# Microcontroller.net
KiCad netlist of a schematic drawn in Altium Designer
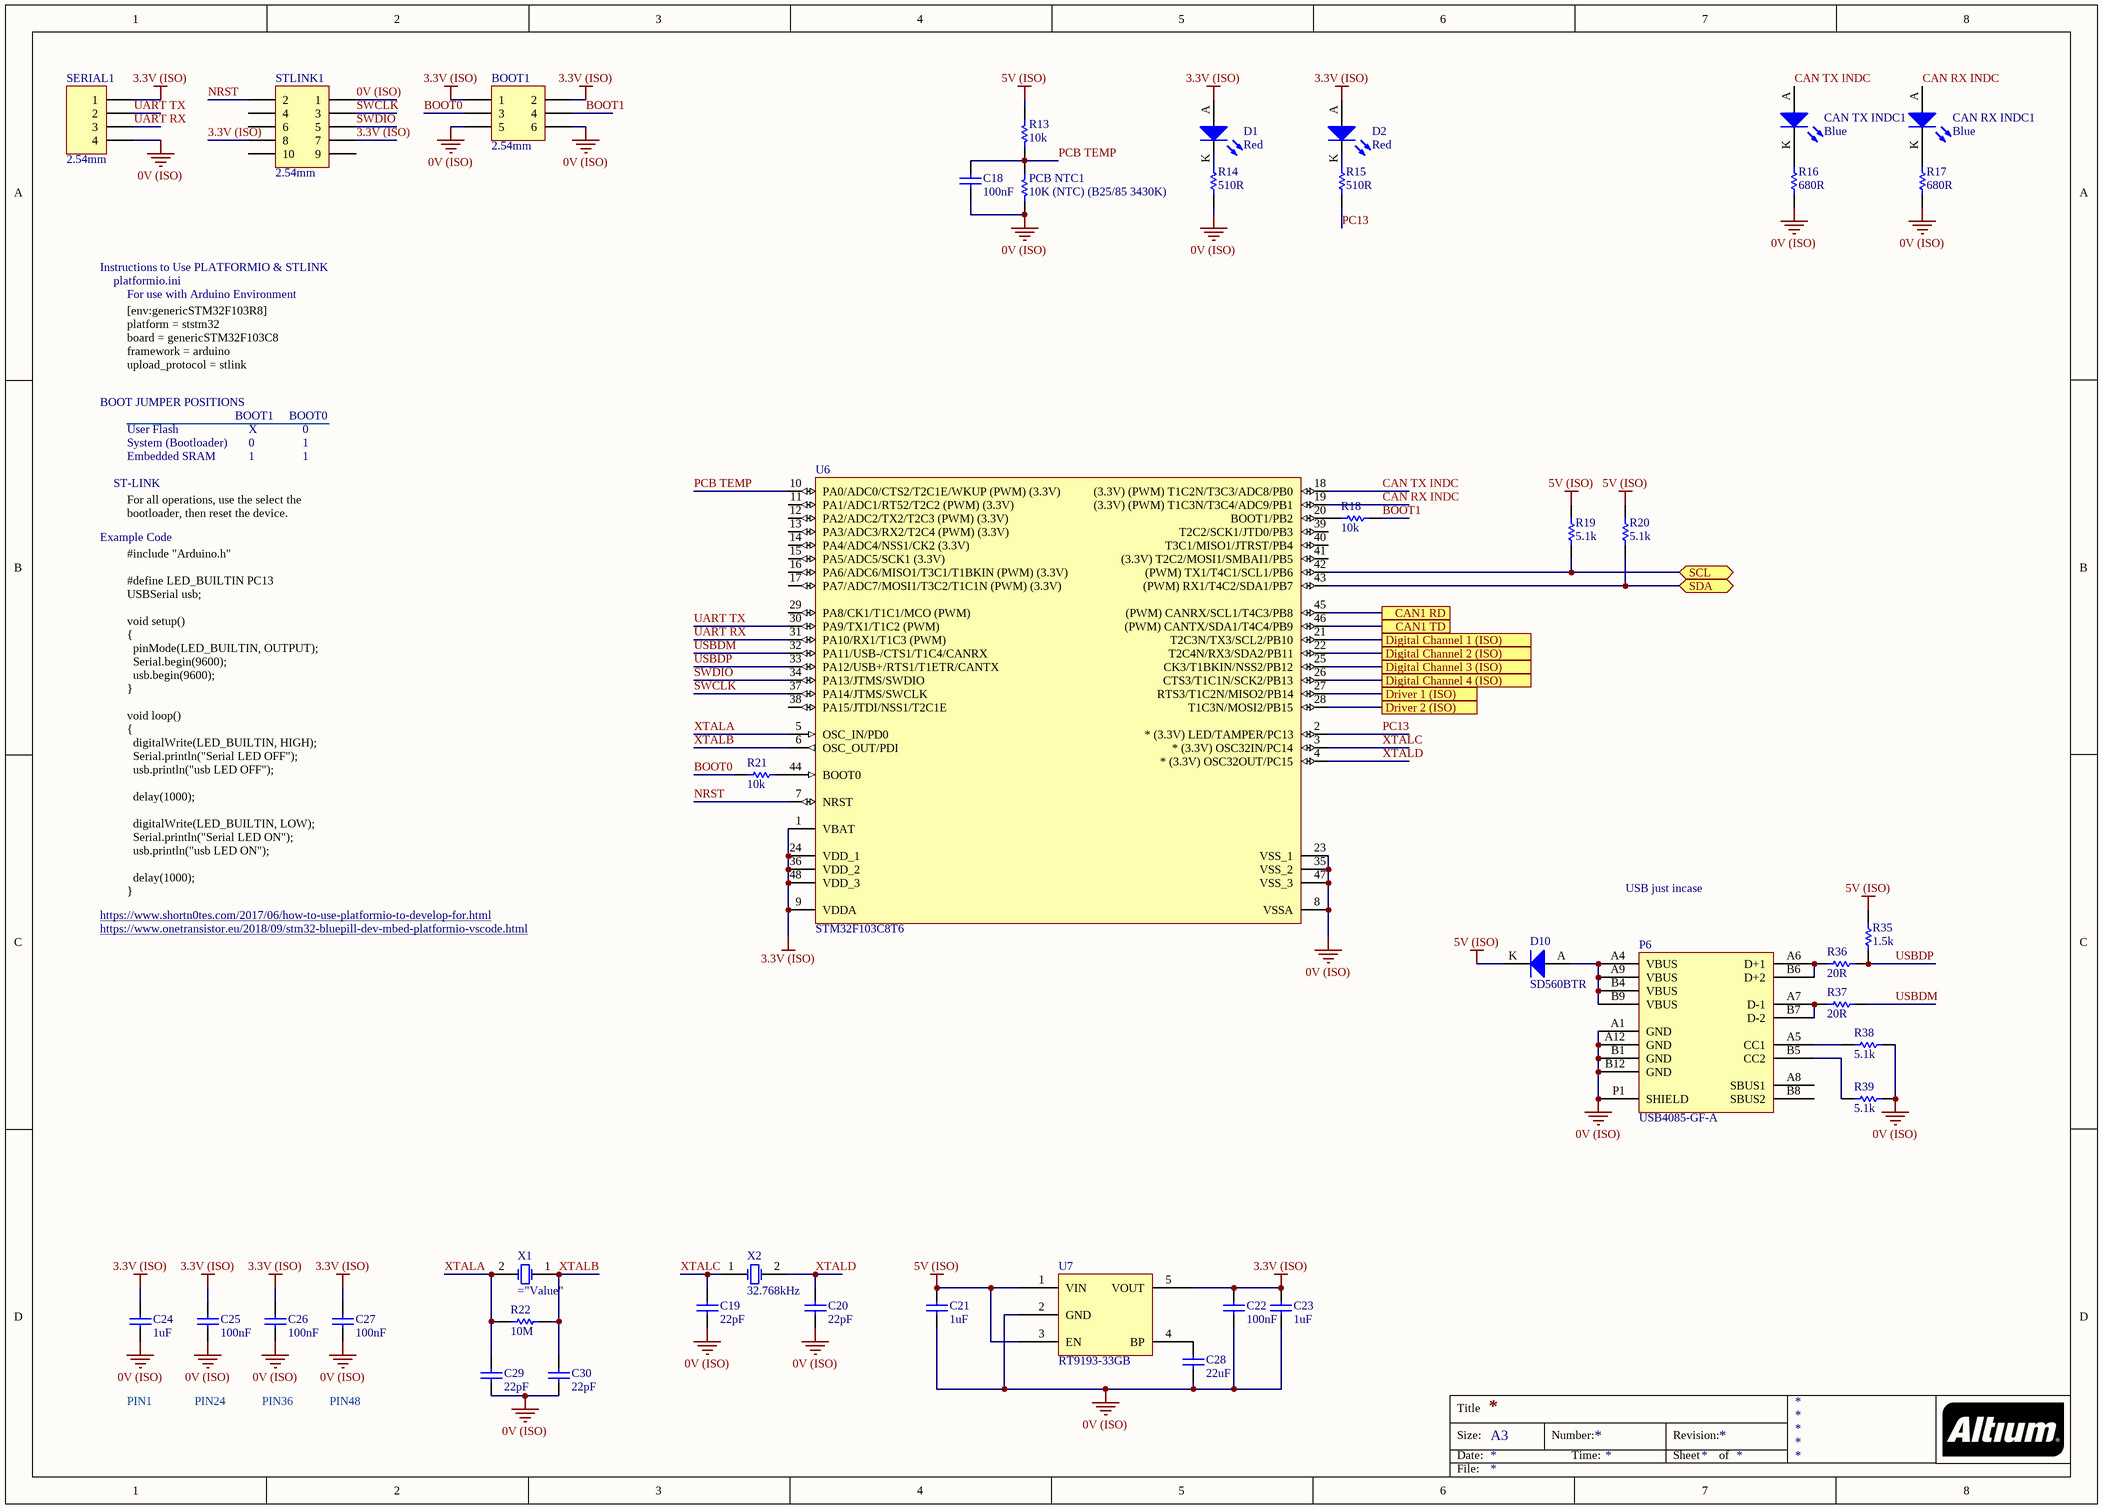
[diagram p0: Microcontroller.SchDoc]

(export (version "E")
  (design (tool "Eeschema 10.0.6"))
  (components
    (comp (ref "BOOT1")
      (value "2.54mm")
      (footprint "TH 2.54mm Header 2x3")
      (fields (field (name "PART NUMBER") "TH 2.54mm Header 2x3") (field (name "CONTACT") "NA"))
      (libsource (lib "ts_20-standard-connectors") (part "Header 2x3"))
    )
    (comp (ref "C18")
      (value "100nF")
      (footprint "0805")
      (fields
        (field (name "PART NUMBER") "GCM21BR71E104KA37L")
        (field (name "TOLERANCE") "10%")
        (field (name "MANUFACTURER") "muRata")
      )
      (libsource (lib "ts_20-standard-library") (part "Capacitor"))
    )
    (comp (ref "C19")
      (value "22pF")
      (footprint "0805")
      (fields
        (field (name "PART NUMBER") "GCM21B5C1H220JA37L")
        (field (name "TOLERANCE") "5%")
        (field (name "MANUFACTURER") "muRata")
      )
      (libsource (lib "ts_20-standard-library") (part "Capacitor"))
    )
    (comp (ref "C20")
      (value "22pF")
      (footprint "0805")
      (fields
        (field (name "PART NUMBER") "GCM21B5C1H220JA37L")
        (field (name "TOLERANCE") "5%")
        (field (name "MANUFACTURER") "muRata")
      )
      (libsource (lib "ts_20-standard-library") (part "Capacitor"))
    )
    (comp (ref "C21")
      (value "1uF")
      (footprint "0805")
      (fields
        (field (name "PART NUMBER") "AC0805KKX7R8BB105")
        (field (name "TOLERANCE") "10%")
        (field (name "MANUFACTURER") "YAGEO")
      )
      (libsource (lib "ts_20-standard-library") (part "Capacitor"))
    )
    (comp (ref "C22")
      (value "100nF")
      (footprint "0805")
      (fields
        (field (name "PART NUMBER") "GCM21BR71E104KA37L")
        (field (name "TOLERANCE") "10%")
        (field (name "MANUFACTURER") "muRata")
      )
      (libsource (lib "ts_20-standard-library") (part "Capacitor"))
    )
    (comp (ref "C23")
      (value "1uF")
      (footprint "0805")
      (fields
        (field (name "PART NUMBER") "AC0805KKX7R8BB105")
        (field (name "TOLERANCE") "10%")
        (field (name "MANUFACTURER") "YAGEO")
      )
      (libsource (lib "ts_20-standard-library") (part "Capacitor"))
    )
    (comp (ref "C24")
      (value "1uF")
      (footprint "0805")
      (fields
        (field (name "PART NUMBER") "AC0805KKX7R8BB105")
        (field (name "TOLERANCE") "10%")
        (field (name "MANUFACTURER") "YAGEO")
      )
      (libsource (lib "ts_20-standard-library") (part "Capacitor"))
    )
    (comp (ref "C25")
      (value "100nF")
      (footprint "0805")
      (fields
        (field (name "PART NUMBER") "GCM21BR71E104KA37L")
        (field (name "TOLERANCE") "10%")
        (field (name "MANUFACTURER") "muRata")
      )
      (libsource (lib "ts_20-standard-library") (part "Capacitor"))
    )
    (comp (ref "C26")
      (value "100nF")
      (footprint "0805")
      (fields
        (field (name "PART NUMBER") "GCM21BR71E104KA37L")
        (field (name "TOLERANCE") "10%")
        (field (name "MANUFACTURER") "muRata")
      )
      (libsource (lib "ts_20-standard-library") (part "Capacitor"))
    )
    (comp (ref "C27")
      (value "100nF")
      (footprint "0805")
      (fields
        (field (name "PART NUMBER") "GCM21BR71E104KA37L")
        (field (name "TOLERANCE") "10%")
        (field (name "MANUFACTURER") "muRata")
      )
      (libsource (lib "ts_20-standard-library") (part "Capacitor"))
    )
    (comp (ref "C28")
      (value "22uF")
      (footprint "0805")
      (fields
        (field (name "PART NUMBER") "GRM21BR61A226ME51L")
        (field (name "TOLERANCE") "20%")
        (field (name "MANUFACTURER") "muRata")
      )
      (libsource (lib "ts_20-standard-library") (part "Capacitor"))
    )
    (comp (ref "C29")
      (value "22pF")
      (footprint "0805")
      (fields
        (field (name "PART NUMBER") "GCM21B5C1H220JA37L")
        (field (name "TOLERANCE") "5%")
        (field (name "MANUFACTURER") "muRata")
      )
      (libsource (lib "ts_20-standard-library") (part "Capacitor"))
    )
    (comp (ref "C30")
      (value "22pF")
      (footprint "0805")
      (fields
        (field (name "PART NUMBER") "GCM21B5C1H220JA37L")
        (field (name "TOLERANCE") "5%")
        (field (name "MANUFACTURER") "muRata")
      )
      (libsource (lib "ts_20-standard-library") (part "Capacitor"))
    )
    (comp (ref "CAN RX INDC1")
      (value "Blue")
      (footprint "0805 LED")
      (description "LED BLUE CLEAR 2012 SMD")
      (fields
        (field (name "PART NUMBER") "SML-MN2BCTT86C")
        (field (name "MANUFACTURER") "ROHM Semiconductor")
      )
      (libsource (lib "ts_20-standard-library") (part "LED"))
    )
    (comp (ref "CAN TX INDC1")
      (value "Blue")
      (footprint "0805 LED")
      (description "LED BLUE CLEAR 2012 SMD")
      (fields
        (field (name "PART NUMBER") "SML-MN2BCTT86C")
        (field (name "MANUFACTURER") "ROHM Semiconductor")
      )
      (libsource (lib "ts_20-standard-library") (part "LED"))
    )
    (comp (ref "D1")
      (value "Red")
      (footprint "0805 LED")
      (description "Red LED Indication - Discrete 1.75V 0805 (2012 Metric)")
      (fields (field (name "MANUFACTURER") "ROHM Semiconductor") (field (name "PART NUMBER") "SML-210LTT86"))
      (libsource (lib "ts_20-standard-library") (part "LED"))
    )
    (comp (ref "D2")
      (value "Red")
      (footprint "0805 LED")
      (description "Red LED Indication - Discrete 1.75V 0805 (2012 Metric)")
      (fields (field (name "MANUFACTURER") "ROHM Semiconductor") (field (name "PART NUMBER") "SML-210LTT86"))
      (libsource (lib "ts_20-standard-library") (part "LED"))
    )
    (comp (ref "D10")
      (value "SD560BTR")
      (footprint "SMB Diode")
      (description "1.2V_F 600V 5A SMB")
      (fields
        (field (name "MANUFACTURER") "SMC Diode Solutions")
        (field (name "DIGIKEY PART NUMBER") "1655-1530-2-ND")
      )
      (libsource (lib "ts_20-standard-library") (part "Diode"))
    )
    (comp (ref "P6")
      (value "USB4085-GF-A")
      (footprint "USB4085-GF-A")
      (description "USB - C (Type - C) USB 2.0 Receptacle Connector 16 Position Through Hole, Right Angle")
      (fields (field (name "DIGIKEY PART NUMBER") "2073-USB4085-GF-ACT-ND"))
      (libsource (lib "ts_20-standard-connectors") (part "USB4085-GF-A"))
    )
    (comp (ref "PCB NTC1")
      (value "10K (NTC) (B25/85 3430K)")
      (footprint "0805")
      (fields
        (field (name "PART NUMBER") "NTCS0805E3103FLT")
        (field (name "MANUFACTURER") "Vishay Beyschlag")
        (field (name "TOLERANCE") "0.01")
      )
      (libsource (lib "ts_20-standard-library") (part "Resistor"))
    )
    (comp (ref "R13")
      (value "10k")
      (footprint "0805")
      (fields
        (field (name "PART NUMBER") "RC0805FR0710KL")
        (field (name "MANUFACTURER") "YAGEO")
        (field (name "TOLERANCE") "0.01")
      )
      (libsource (lib "ts_20-standard-library") (part "Resistor"))
    )
    (comp (ref "R14")
      (value "510R")
      (footprint "0805")
      (fields
        (field (name "MANUFACTURER") "YAGEO")
        (field (name "PART NUMBER") "RC0805FR07510RL")
        (field (name "TOLERANCE") "0.01")
      )
      (libsource (lib "ts_20-standard-library") (part "Resistor"))
    )
    (comp (ref "R15")
      (value "510R")
      (footprint "0805")
      (fields
        (field (name "MANUFACTURER") "YAGEO")
        (field (name "PART NUMBER") "RC0805FR07510RL")
        (field (name "TOLERANCE") "0.01")
      )
      (libsource (lib "ts_20-standard-library") (part "Resistor"))
    )
    (comp (ref "R16")
      (value "680R")
      (footprint "0805")
      (fields
        (field (name "PART NUMBER") "RC0805FR07680RL")
        (field (name "MANUFACTURER") "YAGEO")
        (field (name "TOLERANCE") "0.01")
      )
      (libsource (lib "ts_20-standard-library") (part "Resistor"))
    )
    (comp (ref "R17")
      (value "680R")
      (footprint "0805")
      (fields
        (field (name "PART NUMBER") "RC0805FR07680RL")
        (field (name "MANUFACTURER") "YAGEO")
        (field (name "TOLERANCE") "0.01")
      )
      (libsource (lib "ts_20-standard-library") (part "Resistor"))
    )
    (comp (ref "R18")
      (value "10k")
      (footprint "0805")
      (fields
        (field (name "PART NUMBER") "RC0805FR0710KL")
        (field (name "MANUFACTURER") "YAGEO")
        (field (name "TOLERANCE") "0.01")
      )
      (libsource (lib "ts_20-standard-library") (part "Resistor"))
    )
    (comp (ref "R19")
      (value "5.1k")
      (footprint "0805")
      (fields
        (field (name "PART NUMBER") "RC0805FR075K1L")
        (field (name "MANUFACTURER") "YAGEO")
        (field (name "TOLERANCE") "0.01")
      )
      (libsource (lib "ts_20-standard-library") (part "Resistor"))
    )
    (comp (ref "R20")
      (value "5.1k")
      (footprint "0805")
      (fields
        (field (name "PART NUMBER") "RC0805FR075K1L")
        (field (name "MANUFACTURER") "YAGEO")
        (field (name "TOLERANCE") "0.01")
      )
      (libsource (lib "ts_20-standard-library") (part "Resistor"))
    )
    (comp (ref "R21")
      (value "10k")
      (footprint "0805")
      (fields
        (field (name "PART NUMBER") "RC0805FR0710KL")
        (field (name "MANUFACTURER") "YAGEO")
        (field (name "TOLERANCE") "0.01")
      )
      (libsource (lib "ts_20-standard-library") (part "Resistor"))
    )
    (comp (ref "R22")
      (value "10M")
      (footprint "0805")
      (fields
        (field (name "PART NUMBER") "RC0805FR0710ML")
        (field (name "MANUFACTURER") "YAGEO")
        (field (name "TOLERANCE") "0.01")
      )
      (libsource (lib "ts_20-standard-library") (part "Resistor"))
    )
    (comp (ref "R35")
      (value "1.5k")
      (footprint "0805")
      (fields
        (field (name "PART NUMBER") "RC0805FR071K5L")
        (field (name "MANUFACTURER") "YAGEO")
        (field (name "TOLERANCE") "0.01")
      )
      (libsource (lib "ts_20-standard-library") (part "Resistor"))
    )
    (comp (ref "R36")
      (value "20R")
      (footprint "0805")
      (fields
        (field (name "PART NUMBER") "RC0805FR0720RL")
        (field (name "MANUFACTURER") "YAGEO")
        (field (name "TOLERANCE") "0.01")
      )
      (libsource (lib "ts_20-standard-library") (part "Resistor"))
    )
    (comp (ref "R37")
      (value "20R")
      (footprint "0805")
      (fields
        (field (name "PART NUMBER") "RC0805FR0720RL")
        (field (name "MANUFACTURER") "YAGEO")
        (field (name "TOLERANCE") "0.01")
      )
      (libsource (lib "ts_20-standard-library") (part "Resistor"))
    )
    (comp (ref "R38")
      (value "5.1k")
      (footprint "0805")
      (fields
        (field (name "PART NUMBER") "RC0805FR075K1L")
        (field (name "MANUFACTURER") "YAGEO")
        (field (name "TOLERANCE") "0.01")
      )
      (libsource (lib "ts_20-standard-library") (part "Resistor"))
    )
    (comp (ref "R39")
      (value "5.1k")
      (footprint "0805")
      (fields
        (field (name "PART NUMBER") "RC0805FR075K1L")
        (field (name "MANUFACTURER") "YAGEO")
        (field (name "TOLERANCE") "0.01")
      )
      (libsource (lib "ts_20-standard-library") (part "Resistor"))
    )
    (comp (ref "SERIAL1")
      (value "2.54mm")
      (footprint "TH 2.54mm Header 1x4")
      (fields (field (name "PART NUMBER") "TH 2.54mm Header 1x4") (field (name "CONTACT") "NA"))
      (libsource (lib "ts_20-standard-connectors") (part "Header 1x4"))
    )
    (comp (ref "STLINK1")
      (value "2.54mm")
      (footprint "TH 2.54mm Header 2x5")
      (fields (field (name "PART NUMBER") "TH 2.54mm Header 2x5") (field (name "CONTACT") "NA"))
      (libsource (lib "ts_20-standard-connectors") (part "Header 2x5"))
    )
    (comp (ref "U6")
      (value "STM32F103C8T6")
      (footprint "STM 48-LQFP")
      (description "ARM® Cortex®-M3 STM32F1 Microcontroller IC 32-Bit 72MHz 64KB (64K x 8) FLASH")
      (fields
        (field (name "MANUFACTURER") "STMicroelectronics")
        (field (name "DIGIKEY PART NUMBER") "497-6063-ND")
      )
      (libsource (lib "ts_20-standard-library") (part "STM32F103C8T6"))
    )
    (comp (ref "U7")
      (value "RT9193-33GB")
      (footprint "RICHTEK SOT-23-5")
      (description "IC REG LINEAR 3.3V 300MA SOT23-5")
      (fields (field (name "MANUFACTURER") "Richtek") (field (name "DIGIKEY PART NUMBER") "1028-1014-1-ND"))
      (libsource (lib "ts_20-standard-library") (part "RT9193-33GB"))
    )
    (comp (ref "X1")
      (value "~")
      (footprint "Abracon HC-49/US")
      (fields
        (field (name "PART NUMBER") "ABLS-16.000MHZ-B4-T")
        (field (name "MANUFACTURER") "Abracon LLC")
        (field (name "DIGIKEY PART NUMBER") "535-10226-1-ND")
      )
      (libsource (lib "ts_20-standard-library") (part "Crystal"))
    )
    (comp (ref "X2")
      (value "32.768kHz")
      (footprint "EPSON 2-SMD")
      (fields
        (field (name "PART NUMBER") "FC-135 32.7680KA-A5")
        (field (name "MANUFACTURER") "EPSON")
        (field (name "DIGIKEY PART NUMBER") "SER4103TR-ND")
      )
      (libsource (lib "ts_20-standard-library") (part "Crystal"))
    )
  )
  (nets
    (net (code "1") (name "/BOOT0") (class "Default")
      (node (ref "BOOT1") (pin "3") (pinfunction "3_3") (pintype "passive"))
      (node (ref "R21") (pin "1") (pinfunction "1_1") (pintype "passive"))
    )
    (net (code "2") (name "/BOOT1") (class "Default")
      (node (ref "BOOT1") (pin "4") (pinfunction "4_4") (pintype "passive"))
      (node (ref "R18") (pin "2") (pinfunction "2_2") (pintype "passive"))
    )
    (net (code "3") (name "/CAN RX INDC") (class "Default")
      (node (ref "CAN RX INDC1") (pin "A") (pinfunction "A_A") (pintype "passive"))
      (node (ref "U6") (pin "19") (pinfunction "(3.3V)_(PWM)_T1C3N/T3C4/ADC9/PB1_19") (pintype "bidirectional"))
    )
    (net (code "4") (name "/CAN TX INDC") (class "Default")
      (node (ref "CAN TX INDC1") (pin "A") (pinfunction "A_A") (pintype "passive"))
      (node (ref "U6") (pin "18") (pinfunction "(3.3V)_(PWM)_T1C2N/T3C3/ADC8/PB0_18") (pintype "bidirectional"))
    )
    (net (code "5") (name "/CAN1 RD") (class "Default")
      (node (ref "U6") (pin "45") (pinfunction "(PWM)_CANRX/SCL1/T4C3/PB8_45") (pintype "bidirectional"))
    )
    (net (code "6") (name "/CAN1 TD") (class "Default")
      (node (ref "U6") (pin "46") (pinfunction "(PWM)_CANTX/SDA1/T4C4/PB9_46") (pintype "bidirectional"))
    )
    (net (code "7") (name "/Digital Channel 1 (ISO)") (class "Default")
      (node (ref "U6") (pin "21") (pinfunction "T2C3N/TX3/SCL2/PB10_21") (pintype "bidirectional"))
    )
    (net (code "8") (name "/Digital Channel 2 (ISO)") (class "Default")
      (node (ref "U6") (pin "22") (pinfunction "T2C4N/RX3/SDA2/PB11_22") (pintype "bidirectional"))
    )
    (net (code "9") (name "/Digital Channel 3 (ISO)") (class "Default")
      (node (ref "U6") (pin "25") (pinfunction "CK3/T1BKIN/NSS2/PB12_25") (pintype "bidirectional"))
    )
    (net (code "10") (name "/Digital Channel 4 (ISO)") (class "Default")
      (node (ref "U6") (pin "26") (pinfunction "CTS3/T1C1N/SCK2/PB13_26") (pintype "bidirectional"))
    )
    (net (code "11") (name "/Driver 1 (ISO)") (class "Default")
      (node (ref "U6") (pin "27") (pinfunction "RTS3/T1C2N/MISO2/PB14_27") (pintype "bidirectional"))
    )
    (net (code "12") (name "/Driver 2 (ISO)") (class "Default")
      (node (ref "U6") (pin "28") (pinfunction "T1C3N/MOSI2/PB15_28") (pintype "bidirectional"))
    )
    (net (code "13") (name "/NRST") (class "Default")
      (node (ref "STLINK1") (pin "2") (pinfunction "2_2") (pintype "passive"))
      (node (ref "U6") (pin "7") (pinfunction "NRST_7") (pintype "bidirectional"))
    )
    (net (code "14") (name "/PC13") (class "Default")
      (node (ref "R15") (pin "1") (pinfunction "1_1") (pintype "passive"))
      (node (ref "U6") (pin "2") (pinfunction "*_(3.3V)_LED/TAMPER/PC13_2") (pintype "bidirectional"))
    )
    (net (code "15") (name "/PCB TEMP") (class "Default")
      (node (ref "C18") (pin "2") (pinfunction "2_2") (pintype "passive"))
      (node (ref "PCB NTC1") (pin "2") (pinfunction "2_2") (pintype "passive"))
      (node (ref "R13") (pin "1") (pinfunction "1_1") (pintype "passive"))
      (node (ref "U6") (pin "10") (pinfunction "PA0/ADC0/CTS2/T2C1E/WKUP_(PWM)_(3.3V)_10") (pintype "bidirectional"))
    )
    (net (code "16") (name "/SCL") (class "Default")
      (node (ref "R19") (pin "1") (pinfunction "1_1") (pintype "passive"))
      (node (ref "U6") (pin "42") (pinfunction "(PWM)_TX1/T4C1/SCL1/PB6_42") (pintype "bidirectional"))
    )
    (net (code "17") (name "/SDA") (class "Default")
      (node (ref "R20") (pin "1") (pinfunction "1_1") (pintype "passive"))
      (node (ref "U6") (pin "43") (pinfunction "(PWM)_RX1/T4C2/SDA1/PB7_43") (pintype "bidirectional"))
    )
    (net (code "18") (name "/SWCLK") (class "Default")
      (node (ref "STLINK1") (pin "3") (pinfunction "3_3") (pintype "passive"))
      (node (ref "U6") (pin "37") (pinfunction "PA14/JTMS/SWCLK_37") (pintype "bidirectional"))
    )
    (net (code "19") (name "/SWDIO") (class "Default")
      (node (ref "STLINK1") (pin "5") (pinfunction "5_5") (pintype "passive"))
      (node (ref "U6") (pin "34") (pinfunction "PA13/JTMS/SWDIO_34") (pintype "bidirectional"))
    )
    (net (code "20") (name "/UART RX") (class "Default")
      (node (ref "SERIAL1") (pin "3") (pinfunction "3_3") (pintype "passive"))
      (node (ref "U6") (pin "31") (pinfunction "PA10/RX1/T1C3_(PWM)_31") (pintype "bidirectional"))
    )
    (net (code "21") (name "/UART TX") (class "Default")
      (node (ref "SERIAL1") (pin "2") (pinfunction "2_2") (pintype "passive"))
      (node (ref "U6") (pin "30") (pinfunction "PA9/TX1/T1C2_(PWM)_30") (pintype "bidirectional"))
    )
    (net (code "22") (name "/USBDM") (class "Default")
      (node (ref "R37") (pin "2") (pinfunction "2_2") (pintype "passive"))
      (node (ref "U6") (pin "32") (pinfunction "PA11/USB-/CTS1/T1C4/CANRX_32") (pintype "bidirectional"))
    )
    (net (code "23") (name "/USBDP") (class "Default")
      (node (ref "R35") (pin "1") (pinfunction "1_1") (pintype "passive"))
      (node (ref "R36") (pin "2") (pinfunction "2_2") (pintype "passive"))
      (node (ref "U6") (pin "33") (pinfunction "PA12/USB+/RTS1/T1ETR/CANTX_33") (pintype "bidirectional"))
    )
    (net (code "24") (name "/XTALA") (class "Default")
      (node (ref "C29") (pin "2") (pinfunction "2_2") (pintype "passive"))
      (node (ref "R22") (pin "2") (pinfunction "2_2") (pintype "passive"))
      (node (ref "U6") (pin "5") (pinfunction "OSC_IN/PD0_5") (pintype "input"))
      (node (ref "X1") (pin "2") (pinfunction "OSC2_2") (pintype "passive"))
    )
    (net (code "25") (name "/XTALB") (class "Default")
      (node (ref "C30") (pin "2") (pinfunction "2_2") (pintype "passive"))
      (node (ref "R22") (pin "1") (pinfunction "1_1") (pintype "passive"))
      (node (ref "U6") (pin "6") (pinfunction "OSC_OUT/PDI_6") (pintype "output"))
      (node (ref "X1") (pin "1") (pinfunction "OSC1_1") (pintype "passive"))
    )
    (net (code "26") (name "/XTALC") (class "Default")
      (node (ref "C19") (pin "2") (pinfunction "2_2") (pintype "passive"))
      (node (ref "U6") (pin "3") (pinfunction "*_(3.3V)_OSC32IN/PC14_3") (pintype "bidirectional"))
      (node (ref "X2") (pin "1") (pinfunction "OSC1_1") (pintype "passive"))
    )
    (net (code "27") (name "/XTALD") (class "Default")
      (node (ref "C20") (pin "2") (pinfunction "2_2") (pintype "passive"))
      (node (ref "U6") (pin "4") (pinfunction "*_(3.3V)_OSC32OUT/PC15_4") (pintype "bidirectional"))
      (node (ref "X2") (pin "2") (pinfunction "OSC2_2") (pintype "passive"))
    )
    (net (code "28") (name "0V (ISO)") (class "Default")
      (node (ref "BOOT1") (pin "5") (pinfunction "5_5") (pintype "passive"))
      (node (ref "BOOT1") (pin "6") (pinfunction "6_6") (pintype "passive"))
      (node (ref "C18") (pin "1") (pinfunction "1_1") (pintype "passive"))
      (node (ref "C19") (pin "1") (pinfunction "1_1") (pintype "passive"))
      (node (ref "C20") (pin "1") (pinfunction "1_1") (pintype "passive"))
      (node (ref "C21") (pin "1") (pinfunction "1_1") (pintype "passive"))
      (node (ref "C22") (pin "1") (pinfunction "1_1") (pintype "passive"))
      (node (ref "C23") (pin "1") (pinfunction "1_1") (pintype "passive"))
      (node (ref "C24") (pin "1") (pinfunction "1_1") (pintype "passive"))
      (node (ref "C25") (pin "1") (pinfunction "1_1") (pintype "passive"))
      (node (ref "C26") (pin "1") (pinfunction "1_1") (pintype "passive"))
      (node (ref "C27") (pin "1") (pinfunction "1_1") (pintype "passive"))
      (node (ref "C28") (pin "1") (pinfunction "1_1") (pintype "passive"))
      (node (ref "C29") (pin "1") (pinfunction "1_1") (pintype "passive"))
      (node (ref "C30") (pin "1") (pinfunction "1_1") (pintype "passive"))
      (node (ref "P6") (pin "A1") (pinfunction "GND_A1") (pintype "passive"))
      (node (ref "P6") (pin "A12") (pinfunction "GND_A12") (pintype "passive"))
      (node (ref "P6") (pin "B1") (pinfunction "GND_B1") (pintype "passive"))
      (node (ref "P6") (pin "B12") (pinfunction "GND_B12") (pintype "passive"))
      (node (ref "P6") (pin "P1") (pinfunction "SHIELD_P1") (pintype "passive"))
      (node (ref "PCB NTC1") (pin "1") (pinfunction "1_1") (pintype "passive"))
      (node (ref "R14") (pin "1") (pinfunction "1_1") (pintype "passive"))
      (node (ref "R16") (pin "1") (pinfunction "1_1") (pintype "passive"))
      (node (ref "R17") (pin "1") (pinfunction "1_1") (pintype "passive"))
      (node (ref "R38") (pin "2") (pinfunction "2_2") (pintype "passive"))
      (node (ref "R39") (pin "2") (pinfunction "2_2") (pintype "passive"))
      (node (ref "SERIAL1") (pin "4") (pinfunction "4_4") (pintype "passive"))
      (node (ref "STLINK1") (pin "1") (pinfunction "1_1") (pintype "passive"))
      (node (ref "U6") (pin "23") (pinfunction "VSS_1_23") (pintype "power_in"))
      (node (ref "U6") (pin "35") (pinfunction "VSS_2_35") (pintype "power_in"))
      (node (ref "U6") (pin "47") (pinfunction "VSS_3_47") (pintype "power_in"))
      (node (ref "U6") (pin "8") (pinfunction "VSSA_8") (pintype "power_in"))
      (node (ref "U7") (pin "2") (pinfunction "GND_2") (pintype "passive"))
    )
    (net (code "29") (name "3.3V (ISO)") (class "Default")
      (node (ref "BOOT1") (pin "1") (pinfunction "1_1") (pintype "passive"))
      (node (ref "BOOT1") (pin "2") (pinfunction "2_2") (pintype "passive"))
      (node (ref "C22") (pin "2") (pinfunction "2_2") (pintype "passive"))
      (node (ref "C23") (pin "2") (pinfunction "2_2") (pintype "passive"))
      (node (ref "C24") (pin "2") (pinfunction "2_2") (pintype "passive"))
      (node (ref "C25") (pin "2") (pinfunction "2_2") (pintype "passive"))
      (node (ref "C26") (pin "2") (pinfunction "2_2") (pintype "passive"))
      (node (ref "C27") (pin "2") (pinfunction "2_2") (pintype "passive"))
      (node (ref "D1") (pin "A") (pinfunction "A_A") (pintype "passive"))
      (node (ref "D2") (pin "A") (pinfunction "A_A") (pintype "passive"))
      (node (ref "SERIAL1") (pin "1") (pinfunction "1_1") (pintype "passive"))
      (node (ref "STLINK1") (pin "7") (pinfunction "7_7") (pintype "passive"))
      (node (ref "STLINK1") (pin "8") (pinfunction "8_8") (pintype "passive"))
      (node (ref "U6") (pin "1") (pinfunction "VBAT_1") (pintype "power_in"))
      (node (ref "U6") (pin "24") (pinfunction "VDD_1_24") (pintype "power_in"))
      (node (ref "U6") (pin "36") (pinfunction "VDD_2_36") (pintype "power_in"))
      (node (ref "U6") (pin "48") (pinfunction "VDD_3_48") (pintype "power_in"))
      (node (ref "U6") (pin "9") (pinfunction "VDDA_9") (pintype "power_in"))
      (node (ref "U7") (pin "5") (pinfunction "VOUT_5") (pintype "passive"))
    )
    (net (code "30") (name "5V (ISO)") (class "Default")
      (node (ref "C21") (pin "2") (pinfunction "2_2") (pintype "passive"))
      (node (ref "D10") (pin "K") (pinfunction "K_K") (pintype "passive"))
      (node (ref "R13") (pin "2") (pinfunction "2_2") (pintype "passive"))
      (node (ref "R19") (pin "2") (pinfunction "2_2") (pintype "passive"))
      (node (ref "R20") (pin "2") (pinfunction "2_2") (pintype "passive"))
      (node (ref "R35") (pin "2") (pinfunction "2_2") (pintype "passive"))
      (node (ref "U7") (pin "1") (pinfunction "VIN_1") (pintype "passive"))
      (node (ref "U7") (pin "3") (pinfunction "EN_3") (pintype "passive"))
    )
    (net (code "31") (name "Net-(CAN RX INDC1-PadK)") (class "Default")
      (node (ref "CAN RX INDC1") (pin "K") (pinfunction "K_K") (pintype "passive"))
      (node (ref "R17") (pin "2") (pinfunction "2_2") (pintype "passive"))
    )
    (net (code "32") (name "Net-(CAN TX INDC1-PadK)") (class "Default")
      (node (ref "CAN TX INDC1") (pin "K") (pinfunction "K_K") (pintype "passive"))
      (node (ref "R16") (pin "2") (pinfunction "2_2") (pintype "passive"))
    )
    (net (code "33") (name "Net-(D1-PadK)") (class "Default")
      (node (ref "D1") (pin "K") (pinfunction "K_K") (pintype "passive"))
      (node (ref "R14") (pin "2") (pinfunction "2_2") (pintype "passive"))
    )
    (net (code "34") (name "Net-(D2-PadK)") (class "Default")
      (node (ref "D2") (pin "K") (pinfunction "K_K") (pintype "passive"))
      (node (ref "R15") (pin "2") (pinfunction "2_2") (pintype "passive"))
    )
    (net (code "35") (name "Net-(D10-PadA)") (class "Default")
      (node (ref "D10") (pin "A") (pinfunction "A_A") (pintype "passive"))
      (node (ref "P6") (pin "A4") (pinfunction "VBUS_A4") (pintype "passive"))
      (node (ref "P6") (pin "A9") (pinfunction "VBUS_A9") (pintype "passive"))
      (node (ref "P6") (pin "B4") (pinfunction "VBUS_B4") (pintype "passive"))
      (node (ref "P6") (pin "B9") (pinfunction "VBUS_B9") (pintype "passive"))
    )
    (net (code "36") (name "Net-(P6-CC1)") (class "Default")
      (node (ref "P6") (pin "A5") (pinfunction "CC1_A5") (pintype "passive"))
      (node (ref "R38") (pin "1") (pinfunction "1_1") (pintype "passive"))
    )
    (net (code "37") (name "Net-(P6-CC2)") (class "Default")
      (node (ref "P6") (pin "B5") (pinfunction "CC2_B5") (pintype "passive"))
      (node (ref "R39") (pin "1") (pinfunction "1_1") (pintype "passive"))
    )
    (net (code "38") (name "Net-(P6-D+1)") (class "Default")
      (node (ref "P6") (pin "A6") (pinfunction "D+1_A6") (pintype "passive"))
      (node (ref "P6") (pin "B6") (pinfunction "D+2_B6") (pintype "passive"))
      (node (ref "R36") (pin "1") (pinfunction "1_1") (pintype "passive"))
    )
    (net (code "39") (name "Net-(P6-D-1)") (class "Default")
      (node (ref "P6") (pin "A7") (pinfunction "D-1_A7") (pintype "passive"))
      (node (ref "P6") (pin "B7") (pinfunction "D-2_B7") (pintype "passive"))
      (node (ref "R37") (pin "1") (pinfunction "1_1") (pintype "passive"))
    )
    (net (code "40") (name "Net-(U6-BOOT0)") (class "Default")
      (node (ref "R21") (pin "2") (pinfunction "2_2") (pintype "passive"))
      (node (ref "U6") (pin "44") (pinfunction "BOOT0_44") (pintype "input"))
    )
    (net (code "41") (name "Net-(U6-BOOT1{slash}PB2)") (class "Default")
      (node (ref "R18") (pin "1") (pinfunction "1_1") (pintype "passive"))
      (node (ref "U6") (pin "20") (pinfunction "BOOT1/PB2_20") (pintype "bidirectional"))
    )
    (net (code "42") (name "Net-(U7-BP)") (class "Default")
      (node (ref "C28") (pin "2") (pinfunction "2_2") (pintype "passive"))
      (node (ref "U7") (pin "4") (pinfunction "BP_4") (pintype "passive"))
    )
    (net (code "43") (name "unconnected-(P6-SBUS1-PadA8)") (class "Default")
      (node (ref "P6") (pin "A8") (pinfunction "SBUS1_A8") (pintype "passive"))
    )
    (net (code "44") (name "unconnected-(P6-SBUS2-PadB8)") (class "Default")
      (node (ref "P6") (pin "B8") (pinfunction "SBUS2_B8") (pintype "passive"))
    )
    (net (code "45") (name "unconnected-(STLINK1-Pad4)") (class "Default")
      (node (ref "STLINK1") (pin "4") (pinfunction "4_4") (pintype "passive"))
    )
    (net (code "46") (name "unconnected-(STLINK1-Pad6)") (class "Default")
      (node (ref "STLINK1") (pin "6") (pinfunction "6_6") (pintype "passive"))
    )
    (net (code "47") (name "unconnected-(STLINK1-Pad9)") (class "Default")
      (node (ref "STLINK1") (pin "9") (pinfunction "9_9") (pintype "passive"))
    )
    (net (code "48") (name "unconnected-(STLINK1-Pad10)") (class "Default")
      (node (ref "STLINK1") (pin "10") (pinfunction "10_10") (pintype "passive"))
    )
    (net (code "49") (name "unconnected-(U6-(3.3V)_T2C2{slash}MOSI1{slash}SMBAI1{slash}PB5-Pad41)") (class "Default")
      (node (ref "U6") (pin "41") (pinfunction "(3.3V)_T2C2/MOSI1/SMBAI1/PB5_41") (pintype "bidirectional"))
    )
    (net (code "50") (name "unconnected-(U6-PA1{slash}ADC1{slash}RT52{slash}T2C2_(PWM)_(3.3V)-Pad11)") (class "Default")
      (node (ref "U6") (pin "11") (pinfunction "PA1/ADC1/RT52/T2C2_(PWM)_(3.3V)_11") (pintype "bidirectional"))
    )
    (net (code "51") (name "unconnected-(U6-PA2{slash}ADC2{slash}TX2{slash}T2C3_(PWM)_(3.3V)-Pad12)") (class "Default")
      (node (ref "U6") (pin "12") (pinfunction "PA2/ADC2/TX2/T2C3_(PWM)_(3.3V)_12") (pintype "bidirectional"))
    )
    (net (code "52") (name "unconnected-(U6-PA3{slash}ADC3{slash}RX2{slash}T2C4_(PWM)_(3.3V)-Pad13)") (class "Default")
      (node (ref "U6") (pin "13") (pinfunction "PA3/ADC3/RX2/T2C4_(PWM)_(3.3V)_13") (pintype "bidirectional"))
    )
    (net (code "53") (name "unconnected-(U6-PA4{slash}ADC4{slash}NSS1{slash}CK2_(3.3V)-Pad14)") (class "Default")
      (node (ref "U6") (pin "14") (pinfunction "PA4/ADC4/NSS1/CK2_(3.3V)_14") (pintype "bidirectional"))
    )
    (net (code "54") (name "unconnected-(U6-PA5{slash}ADC5{slash}SCK1_(3.3V)-Pad15)") (class "Default")
      (node (ref "U6") (pin "15") (pinfunction "PA5/ADC5/SCK1_(3.3V)_15") (pintype "bidirectional"))
    )
    (net (code "55") (name "unconnected-(U6-PA6{slash}ADC6{slash}MISO1{slash}T3C1{slash}T1BKIN_(PWM)_(3.3V)-Pad16)") (class "Default")
      (node (ref "U6") (pin "16") (pinfunction "PA6/ADC6/MISO1/T3C1/T1BKIN_(PWM)_(3.3V)_16") (pintype "bidirectional"))
    )
    (net (code "56") (name "unconnected-(U6-PA7{slash}ADC7{slash}MOSI1{slash}T3C2{slash}T1C1N_(PWM)_(3.3V)-Pad17)") (class "Default")
      (node (ref "U6") (pin "17") (pinfunction "PA7/ADC7/MOSI1/T3C2/T1C1N_(PWM)_(3.3V)_17") (pintype "bidirectional"))
    )
    (net (code "57") (name "unconnected-(U6-PA8{slash}CK1{slash}T1C1{slash}MCO_(PWM)-Pad29)") (class "Default")
      (node (ref "U6") (pin "29") (pinfunction "PA8/CK1/T1C1/MCO_(PWM)_29") (pintype "bidirectional"))
    )
    (net (code "58") (name "unconnected-(U6-PA15{slash}JTDI{slash}NSS1{slash}T2C1E-Pad38)") (class "Default")
      (node (ref "U6") (pin "38") (pinfunction "PA15/JTDI/NSS1/T2C1E_38") (pintype "bidirectional"))
    )
    (net (code "59") (name "unconnected-(U6-T2C2{slash}SCK1{slash}JTD0{slash}PB3-Pad39)") (class "Default")
      (node (ref "U6") (pin "39") (pinfunction "T2C2/SCK1/JTD0/PB3_39") (pintype "bidirectional"))
    )
    (net (code "60") (name "unconnected-(U6-T3C1{slash}MISO1{slash}JTRST{slash}PB4-Pad40)") (class "Default")
      (node (ref "U6") (pin "40") (pinfunction "T3C1/MISO1/JTRST/PB4_40") (pintype "bidirectional"))
    )
  )
)
